# courtyard_power.net
KiCad netlist of a schematic drawn in EAGLE
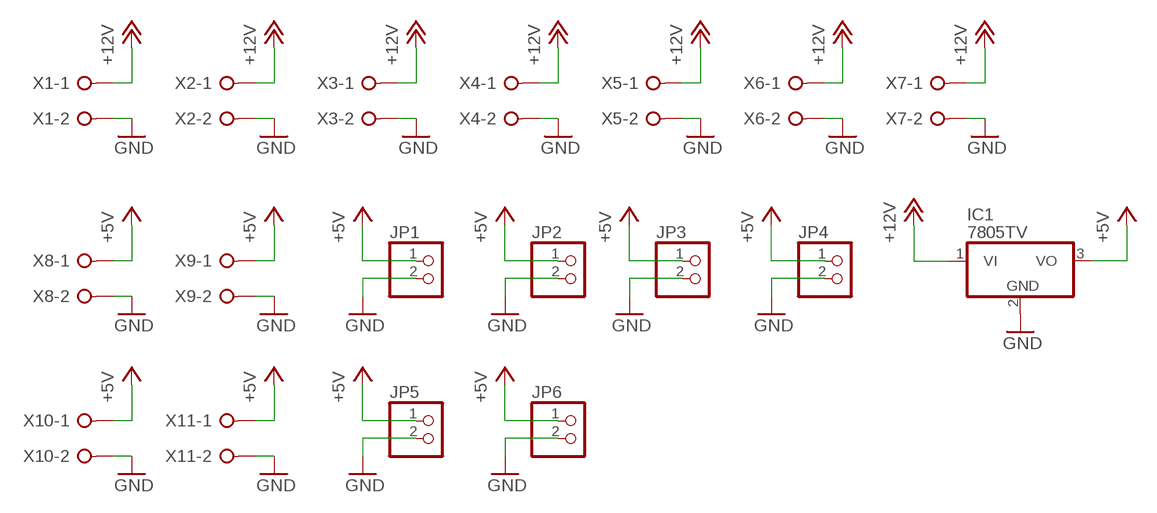
[diagram p0: schematic, sheet 1]

(export (version "E")
  (design (tool "Eeschema 10.0.6"))
  (components
    (comp (ref "IC1")
      (value "7805TV")
      (footprint "eagle-import:TO220V")
      (libsource (lib "eagle-import") (part "78TV05"))
    )
    (comp (ref "JP1")
      (value "PINHD-1X2")
      (footprint "eagle-import:1X02")
      (libsource (lib "eagle-import") (part "PINHD-1X2"))
    )
    (comp (ref "JP2")
      (value "PINHD-1X2")
      (footprint "eagle-import:1X02")
      (libsource (lib "eagle-import") (part "PINHD-1X2"))
    )
    (comp (ref "JP3")
      (value "PINHD-1X2")
      (footprint "eagle-import:1X02")
      (libsource (lib "eagle-import") (part "PINHD-1X2"))
    )
    (comp (ref "JP4")
      (value "PINHD-1X2")
      (footprint "eagle-import:1X02")
      (libsource (lib "eagle-import") (part "PINHD-1X2"))
    )
    (comp (ref "JP5")
      (value "PINHD-1X2")
      (footprint "eagle-import:1X02")
      (libsource (lib "eagle-import") (part "PINHD-1X2"))
    )
    (comp (ref "JP6")
      (value "PINHD-1X2")
      (footprint "eagle-import:1X02")
      (libsource (lib "eagle-import") (part "PINHD-1X2"))
    )
    (comp (ref "X1")
      (value "W237-02P")
      (footprint "eagle-import:W237-132")
      (libsource (lib "eagle-import") (part "W237-02P"))
    )
    (comp (ref "X2")
      (value "W237-02P")
      (footprint "eagle-import:W237-132")
      (libsource (lib "eagle-import") (part "W237-02P"))
    )
    (comp (ref "X3")
      (value "W237-02P")
      (footprint "eagle-import:W237-132")
      (libsource (lib "eagle-import") (part "W237-02P"))
    )
    (comp (ref "X4")
      (value "W237-02P")
      (footprint "eagle-import:W237-132")
      (libsource (lib "eagle-import") (part "W237-02P"))
    )
    (comp (ref "X5")
      (value "W237-02P")
      (footprint "eagle-import:W237-132")
      (libsource (lib "eagle-import") (part "W237-02P"))
    )
    (comp (ref "X6")
      (value "W237-02P")
      (footprint "eagle-import:W237-132")
      (libsource (lib "eagle-import") (part "W237-02P"))
    )
    (comp (ref "X7")
      (value "W237-02P")
      (footprint "eagle-import:W237-132")
      (libsource (lib "eagle-import") (part "W237-02P"))
    )
    (comp (ref "X8")
      (value "W237-02P")
      (footprint "eagle-import:W237-132")
      (libsource (lib "eagle-import") (part "W237-02P"))
    )
    (comp (ref "X9")
      (value "W237-02P")
      (footprint "eagle-import:W237-132")
      (libsource (lib "eagle-import") (part "W237-02P"))
    )
    (comp (ref "X10")
      (value "W237-02P")
      (footprint "eagle-import:W237-132")
      (libsource (lib "eagle-import") (part "W237-02P"))
    )
    (comp (ref "X11")
      (value "W237-02P")
      (footprint "eagle-import:W237-132")
      (libsource (lib "eagle-import") (part "W237-02P"))
    )
  )
  (nets
    (net (code "1") (name "+5V") (class "Default")
      (node (ref "IC1") (pin "3") (pinfunction "VO_3") (pintype "passive"))
      (node (ref "JP1") (pin "1") (pinfunction "1_1") (pintype "passive"))
      (node (ref "JP2") (pin "1") (pinfunction "1_1") (pintype "passive"))
      (node (ref "JP3") (pin "1") (pinfunction "1_1") (pintype "passive"))
      (node (ref "JP4") (pin "1") (pinfunction "1_1") (pintype "passive"))
      (node (ref "JP5") (pin "1") (pinfunction "1_1") (pintype "passive"))
      (node (ref "JP6") (pin "1") (pinfunction "1_1") (pintype "passive"))
      (node (ref "X10") (pin "1") (pinfunction "KL_1") (pintype "passive"))
      (node (ref "X11") (pin "1") (pinfunction "KL_1") (pintype "passive"))
      (node (ref "X8") (pin "1") (pinfunction "KL_1") (pintype "passive"))
      (node (ref "X9") (pin "1") (pinfunction "KL_1") (pintype "passive"))
    )
    (net (code "2") (name "+12V") (class "Default")
      (node (ref "IC1") (pin "1") (pinfunction "VI_1") (pintype "input"))
      (node (ref "X1") (pin "1") (pinfunction "KL_1") (pintype "passive"))
      (node (ref "X2") (pin "1") (pinfunction "KL_1") (pintype "passive"))
      (node (ref "X3") (pin "1") (pinfunction "KL_1") (pintype "passive"))
      (node (ref "X4") (pin "1") (pinfunction "KL_1") (pintype "passive"))
      (node (ref "X5") (pin "1") (pinfunction "KL_1") (pintype "passive"))
      (node (ref "X6") (pin "1") (pinfunction "KL_1") (pintype "passive"))
      (node (ref "X7") (pin "1") (pinfunction "KL_1") (pintype "passive"))
    )
    (net (code "3") (name "GND") (class "Default")
      (node (ref "IC1") (pin "2") (pinfunction "GND_2") (pintype "passive"))
      (node (ref "JP1") (pin "2") (pinfunction "2_2") (pintype "passive"))
      (node (ref "JP2") (pin "2") (pinfunction "2_2") (pintype "passive"))
      (node (ref "JP3") (pin "2") (pinfunction "2_2") (pintype "passive"))
      (node (ref "JP4") (pin "2") (pinfunction "2_2") (pintype "passive"))
      (node (ref "JP5") (pin "2") (pinfunction "2_2") (pintype "passive"))
      (node (ref "JP6") (pin "2") (pinfunction "2_2") (pintype "passive"))
      (node (ref "X1") (pin "2") (pinfunction "KL_2") (pintype "passive"))
      (node (ref "X10") (pin "2") (pinfunction "KL_2") (pintype "passive"))
      (node (ref "X11") (pin "2") (pinfunction "KL_2") (pintype "passive"))
      (node (ref "X2") (pin "2") (pinfunction "KL_2") (pintype "passive"))
      (node (ref "X3") (pin "2") (pinfunction "KL_2") (pintype "passive"))
      (node (ref "X4") (pin "2") (pinfunction "KL_2") (pintype "passive"))
      (node (ref "X5") (pin "2") (pinfunction "KL_2") (pintype "passive"))
      (node (ref "X6") (pin "2") (pinfunction "KL_2") (pintype "passive"))
      (node (ref "X7") (pin "2") (pinfunction "KL_2") (pintype "passive"))
      (node (ref "X8") (pin "2") (pinfunction "KL_2") (pintype "passive"))
      (node (ref "X9") (pin "2") (pinfunction "KL_2") (pintype "passive"))
    )
  )
)
